# C51.net
KiCad netlist of a schematic drawn in EasyEDA Pro
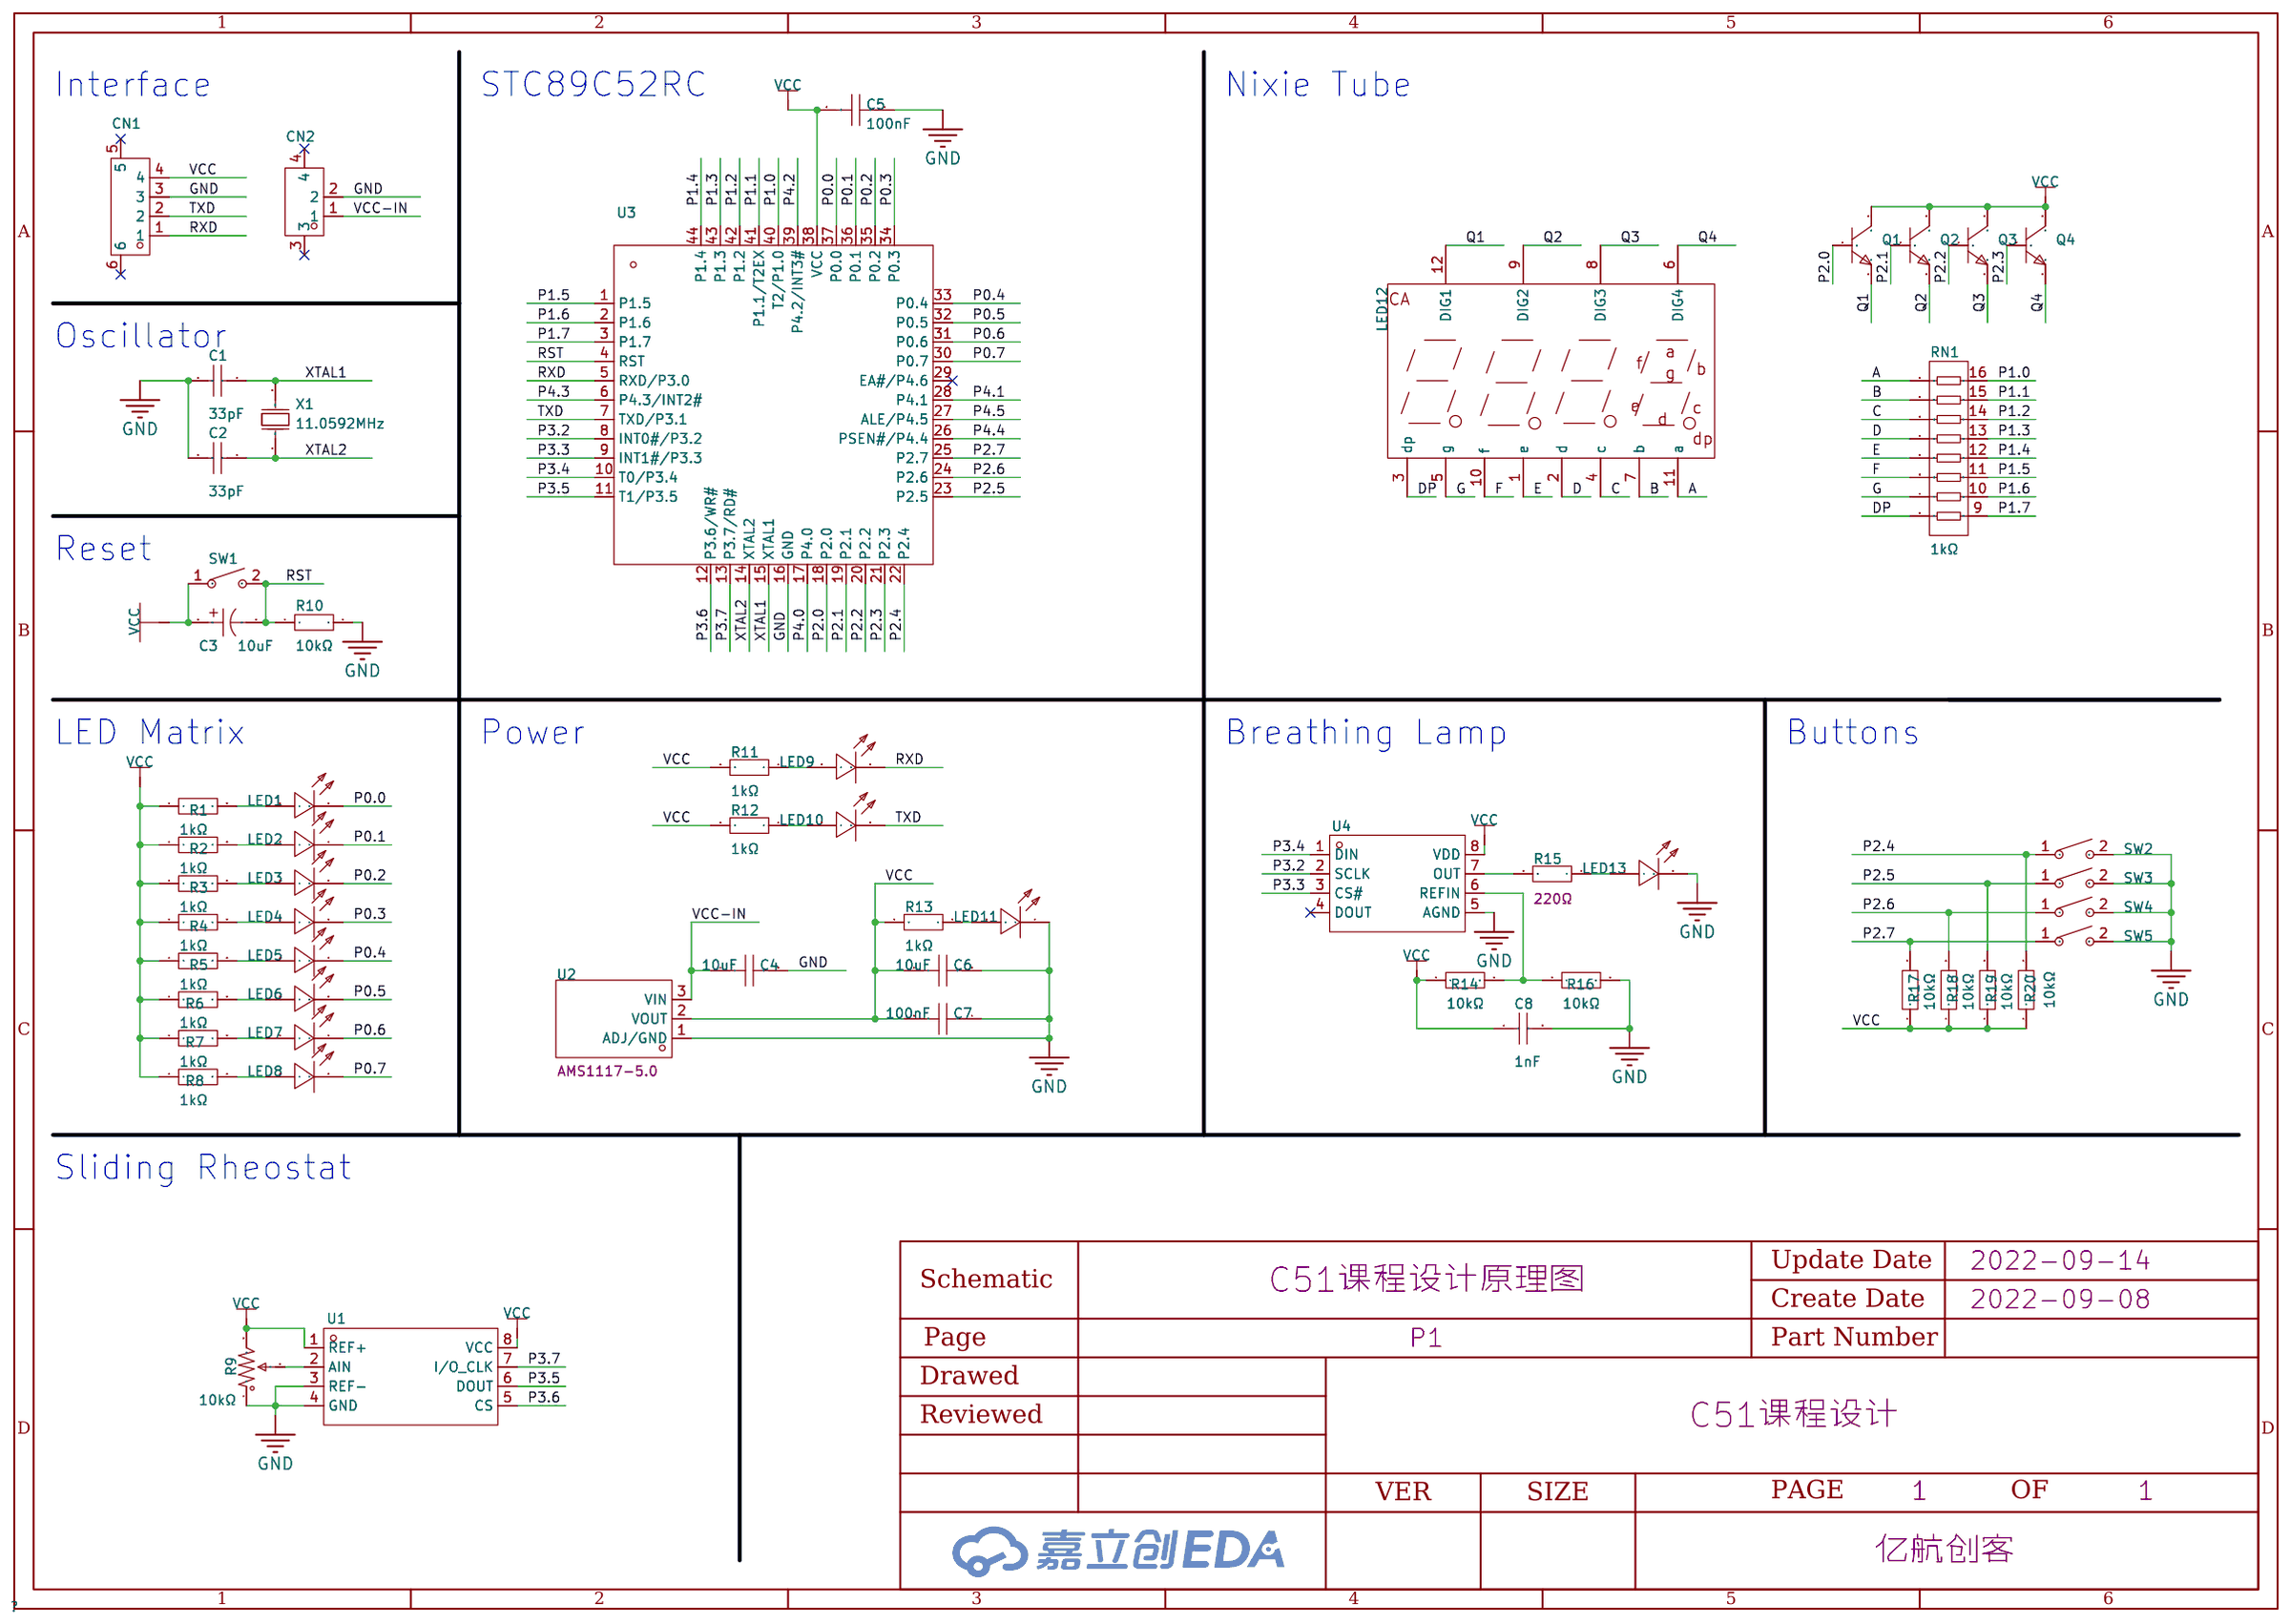
[diagram p0: schematic sheet]

(export (version "E")
  (design (tool "Eeschema 10.0.6"))
  (components
    (comp (ref "C1")
      (value "33pF")
      (footprint "easyedapro:C0402")
      (description "容值:33pF;精度:±5%;额定电压:50V;材质(温度系数):NP0;")
      (fields
        (field (name "Manufacturer Part") "CC0402JRNPO9BN330")
        (field (name "Manufacturer") "YAGEO(国巨)")
      )
      (libsource (lib "easyedapro") (part "CC0402JRNPO9BN330"))
    )
    (comp (ref "C2")
      (value "33pF")
      (footprint "easyedapro:C0402")
      (description "容值:33pF;精度:±5%;额定电压:50V;材质(温度系数):NP0;")
      (fields
        (field (name "Manufacturer Part") "CC0402JRNPO9BN330")
        (field (name "Manufacturer") "YAGEO(国巨)")
      )
      (libsource (lib "easyedapro") (part "CC0402JRNPO9BN330"))
    )
    (comp (ref "C3")
      (value "10uF")
      (footprint "easyedapro:CAP-SMD_L2.0-W1.3-FD")
      (description "容值:10uF;精度:±10%;额定电压:6.3V;漏电流:-;纹波电流:-;等效串联电阻:-;工作温度:-;")
      (fields
        (field (name "Manufacturer Part") "CA45-P-6.3V-10UF-K")
        (field (name "Manufacturer") "CEC(振华新云)")
      )
      (libsource (lib "easyedapro") (part "CA45-P-6.3V-10UF-K"))
    )
    (comp (ref "C4")
      (value "10uF")
      (footprint "easyedapro:C0402")
      (description "容值:10uF;精度:±20%;额定电压:-;温度系数:-;")
      (fields
        (field (name "Manufacturer Part") "ZRB15XR60J106ME12D")
        (field (name "Manufacturer") "muRata(村田)")
      )
      (libsource (lib "easyedapro") (part "ZRB15XR60J106ME12D"))
    )
    (comp (ref "C5")
      (value "100nF")
      (footprint "easyedapro:C0402")
      (description "容值:100nF;精度:±10%;额定电压:50V;材质(温度系数):X7R;")
      (fields (field (name "Manufacturer Part") "C1005X7R1H104KT000F") (field (name "Manufacturer") "TDK"))
      (libsource (lib "easyedapro") (part "C1005X7R1H104KT000F"))
    )
    (comp (ref "C6")
      (value "10uF")
      (footprint "easyedapro:C0402")
      (description "容值:10uF;精度:±20%;额定电压:-;温度系数:-;")
      (fields
        (field (name "Manufacturer Part") "ZRB15XR60J106ME12D")
        (field (name "Manufacturer") "muRata(村田)")
      )
      (libsource (lib "easyedapro") (part "ZRB15XR60J106ME12D"))
    )
    (comp (ref "C7")
      (value "100nF")
      (description "容值:100nF;精度:±10%;额定电压:50V;温度系数:X7R;")
      (fields (field (name "Manufacturer Part") "C1005X7R1H104KT000F") (field (name "Manufacturer") "TDK"))
      (libsource (lib "easyedapro") (part "C1005X7R1H104KT000F"))
    )
    (comp (ref "C8")
      (value "1nF")
      (footprint "easyedapro:C0402")
      (description "温度系数:X7R;容值:1nF;精度:±10%;额定电压:50V;")
      (fields (field (name "Manufacturer Part") "0402B102K500NT") (field (name "Manufacturer") "FH(风华)"))
      (libsource (lib "easyedapro") (part "0402B102K500NT"))
    )
    (comp (ref "CN1")
      (value "~")
      (footprint "easyedapro:CONN-SMD_4P-P1.00_HDGC_HDGC1002WR-S-4P")
      (description "参考系列:-;间距:1mm;插针结构:1x4P;排数:1;每排PIN数:4;行距:-;公母:公型插针;安装方式:卧贴;额定电流:1A;工作温度范围:-25~+70;")
      (fields (field (name "Manufacturer Part") "HDGC1002WR-S-4P") (field (name "Manufacturer") "HDGC(华德共创)"))
      (libsource (lib "easyedapro") (part "HDGC1002WR-S-4P"))
    )
    (comp (ref "CN2")
      (value "~")
      (footprint "easyedapro:CONN-SMD_HC-1.0-2PWT")
      (description "参考系列:-;间距:1mm;插针结构:1x2P;排数:1;每排PIN数:2;行距:-;公母:公型插针;安装方式:卧贴;额定电流:500mA;工作温度范围:-25~+85;")
      (fields (field (name "Manufacturer Part") "HC-1.0-2PWT") (field (name "Manufacturer") "HCTL(华灿天禄)"))
      (libsource (lib "easyedapro") (part "HC-1.0-2PWT"))
    )
    (comp (ref "LED1")
      (value "~")
      (footprint "easyedapro:LED0402-RD")
      (description "发光颜色:翠绿;")
      (fields (field (name "Manufacturer Part") "NCD0402G1") (field (name "Manufacturer") "国星光电"))
      (libsource (lib "easyedapro") (part "FC-F1005UGK-520M5"))
    )
    (comp (ref "LED2")
      (value "~")
      (footprint "easyedapro:LED0402-RD")
      (description "发光颜色:翠绿;")
      (fields (field (name "Manufacturer Part") "NCD0402G1") (field (name "Manufacturer") "国星光电"))
      (libsource (lib "easyedapro") (part "FC-F1005UGK-520M5"))
    )
    (comp (ref "LED3")
      (value "~")
      (footprint "easyedapro:LED0402-RD")
      (description "发光颜色:翠绿;")
      (fields (field (name "Manufacturer Part") "NCD0402G1") (field (name "Manufacturer") "国星光电"))
      (libsource (lib "easyedapro") (part "FC-F1005UGK-520M5"))
    )
    (comp (ref "LED4")
      (value "~")
      (footprint "easyedapro:LED0402-RD")
      (description "发光颜色:翠绿;")
      (fields (field (name "Manufacturer Part") "NCD0402G1") (field (name "Manufacturer") "国星光电"))
      (libsource (lib "easyedapro") (part "FC-F1005UGK-520M5"))
    )
    (comp (ref "LED5")
      (value "~")
      (footprint "easyedapro:LED0402-RD")
      (description "发光颜色:翠绿;")
      (fields (field (name "Manufacturer Part") "NCD0402G1") (field (name "Manufacturer") "国星光电"))
      (libsource (lib "easyedapro") (part "FC-F1005UGK-520M5"))
    )
    (comp (ref "LED6")
      (value "~")
      (footprint "easyedapro:LED0402-RD")
      (description "发光颜色:翠绿;")
      (fields (field (name "Manufacturer Part") "NCD0402G1") (field (name "Manufacturer") "国星光电"))
      (libsource (lib "easyedapro") (part "FC-F1005UGK-520M5"))
    )
    (comp (ref "LED7")
      (value "~")
      (footprint "easyedapro:LED0402-RD")
      (description "发光颜色:翠绿;")
      (fields (field (name "Manufacturer Part") "NCD0402G1") (field (name "Manufacturer") "国星光电"))
      (libsource (lib "easyedapro") (part "FC-F1005UGK-520M5"))
    )
    (comp (ref "LED8")
      (value "~")
      (footprint "easyedapro:LED0402-RD")
      (description "发光颜色:翠绿;")
      (fields (field (name "Manufacturer Part") "NCD0402G1") (field (name "Manufacturer") "国星光电"))
      (libsource (lib "easyedapro") (part "FC-F1005UGK-520M5"))
    )
    (comp (ref "LED9")
      (value "~")
      (footprint "easyedapro:LED0402-RD")
      (description "发光颜色:翠绿;")
      (fields (field (name "Manufacturer Part") "NCD0402G1") (field (name "Manufacturer") "国星光电"))
      (libsource (lib "easyedapro") (part "FC-F1005UGK-520M5"))
    )
    (comp (ref "LED10")
      (value "~")
      (footprint "easyedapro:LED0402-RD")
      (description "发光颜色:翠绿;")
      (fields (field (name "Manufacturer Part") "NCD0402G1") (field (name "Manufacturer") "国星光电"))
      (libsource (lib "easyedapro") (part "FC-F1005UGK-520M5"))
    )
    (comp (ref "LED11")
      (value "~")
      (footprint "easyedapro:LED0402-RD")
      (description "发光颜色:翠绿;")
      (fields (field (name "Manufacturer Part") "NCD0402G1") (field (name "Manufacturer") "国星光电"))
      (libsource (lib "easyedapro") (part "FC-F1005UGK-520M5"))
    )
    (comp (ref "LED12")
      (value "FJ2481BH")
      (footprint "easyedapro:LED-SEG-TH_FJ2481BH")
      (description "数码管位数:4;数码管的显示尺寸:0.28''(7.11mm);电路连线类型:阳极(正极);照明颜色:红色;")
      (fields (field (name "Manufacturer") "志浩"))
      (libsource (lib "easyedapro") (part "FJ2481BH"))
    )
    (comp (ref "LED13")
      (value "~")
      (footprint "easyedapro:LED0402-RD")
      (description "发光颜色:翠绿;")
      (fields (field (name "Manufacturer Part") "NCD0402G1") (field (name "Manufacturer") "国星光电"))
      (libsource (lib "easyedapro") (part "FC-F1005UGK-520M5"))
    )
    (comp (ref "Q1")
      (value "SS8050W Y1")
      (footprint "easyedapro:SOT-323-3_L2.1-W1.3-P1.30-LS2.3-BR")
      (fields (field (name "Manufacturer") "CBI(创基)"))
      (libsource (lib "easyedapro") (part "SS8050W"))
    )
    (comp (ref "Q2")
      (value "SS8050W Y1")
      (footprint "easyedapro:SOT-323-3_L2.1-W1.3-P1.30-LS2.3-BR")
      (fields (field (name "Manufacturer") "CBI(创基)"))
      (libsource (lib "easyedapro") (part "SS8050W"))
    )
    (comp (ref "Q3")
      (value "SS8050W Y1")
      (footprint "easyedapro:SOT-323-3_L2.1-W1.3-P1.30-LS2.3-BR")
      (fields (field (name "Manufacturer") "CBI(创基)"))
      (libsource (lib "easyedapro") (part "SS8050W"))
    )
    (comp (ref "Q4")
      (value "SS8050W Y1")
      (footprint "easyedapro:SOT-323-3_L2.1-W1.3-P1.30-LS2.3-BR")
      (fields (field (name "Manufacturer") "CBI(创基)"))
      (libsource (lib "easyedapro") (part "SS8050W"))
    )
    (comp (ref "R1")
      (value "1kΩ")
      (footprint "easyedapro:R0402")
      (description "阻值:10kΩ;精度:±1%;功率:1/16W;温度系数:±100ppm/;最大工作电压:50V;工作温度范围:-55~+155;")
      (fields (field (name "Manufacturer Part") "WR04X1002FTL") (field (name "Manufacturer") "华新科(Walsin)"))
      (libsource (lib "easyedapro") (part "WR04X1002FTL"))
    )
    (comp (ref "R2")
      (value "1kΩ")
      (footprint "easyedapro:R0402")
      (description "阻值:10kΩ;精度:±1%;功率:1/16W;温度系数:±100ppm/;最大工作电压:50V;工作温度范围:-55~+155;")
      (fields (field (name "Manufacturer Part") "WR04X1002FTL") (field (name "Manufacturer") "华新科(Walsin)"))
      (libsource (lib "easyedapro") (part "WR04X1002FTL"))
    )
    (comp (ref "R3")
      (value "1kΩ")
      (footprint "easyedapro:R0402")
      (description "阻值:10kΩ;精度:±1%;功率:1/16W;温度系数:±100ppm/;最大工作电压:50V;工作温度范围:-55~+155;")
      (fields (field (name "Manufacturer Part") "WR04X1002FTL") (field (name "Manufacturer") "华新科(Walsin)"))
      (libsource (lib "easyedapro") (part "WR04X1002FTL"))
    )
    (comp (ref "R4")
      (value "1kΩ")
      (footprint "easyedapro:R0402")
      (description "阻值:10kΩ;精度:±1%;功率:1/16W;温度系数:±100ppm/;最大工作电压:50V;工作温度范围:-55~+155;")
      (fields (field (name "Manufacturer Part") "WR04X1002FTL") (field (name "Manufacturer") "华新科(Walsin)"))
      (libsource (lib "easyedapro") (part "WR04X1002FTL"))
    )
    (comp (ref "R5")
      (value "1kΩ")
      (footprint "easyedapro:R0402")
      (description "阻值:10kΩ;精度:±1%;功率:1/16W;温度系数:±100ppm/;最大工作电压:50V;工作温度范围:-55~+155;")
      (fields (field (name "Manufacturer Part") "WR04X1002FTL") (field (name "Manufacturer") "华新科(Walsin)"))
      (libsource (lib "easyedapro") (part "WR04X1002FTL"))
    )
    (comp (ref "R6")
      (value "1kΩ")
      (footprint "easyedapro:R0402")
      (description "阻值:10kΩ;精度:±1%;功率:1/16W;温度系数:±100ppm/;最大工作电压:50V;工作温度范围:-55~+155;")
      (fields (field (name "Manufacturer Part") "WR04X1002FTL") (field (name "Manufacturer") "华新科(Walsin)"))
      (libsource (lib "easyedapro") (part "WR04X1002FTL"))
    )
    (comp (ref "R7")
      (value "1kΩ")
      (footprint "easyedapro:R0402")
      (description "阻值:10kΩ;精度:±1%;功率:1/16W;温度系数:±100ppm/;最大工作电压:50V;工作温度范围:-55~+155;")
      (fields (field (name "Manufacturer Part") "WR04X1002FTL") (field (name "Manufacturer") "华新科(Walsin)"))
      (libsource (lib "easyedapro") (part "WR04X1002FTL"))
    )
    (comp (ref "R8")
      (value "1kΩ")
      (footprint "easyedapro:R0402")
      (description "阻值:10kΩ;精度:±1%;功率:1/16W;温度系数:±100ppm/;最大工作电压:50V;工作温度范围:-55~+155;")
      (fields (field (name "Manufacturer Part") "WR04X1002FTL") (field (name "Manufacturer") "华新科(Walsin)"))
      (libsource (lib "easyedapro") (part "WR04X1002FTL"))
    )
    (comp (ref "R9")
      (value "10kΩ")
      (footprint "easyedapro:RES-ADJ-TH_3362P")
      (description "阻值:10kΩ;精度:±10%;温度系数:±250ppm/;")
      (fields (field (name "Manufacturer Part") "3362P-1-103") (field (name "Manufacturer") "BOCHEN(博晨)"))
      (libsource (lib "easyedapro") (part "3362P-1-103_C118956"))
    )
    (comp (ref "R10")
      (value "10kΩ")
      (footprint "easyedapro:R0402")
      (description "阻值:10kΩ;精度:±1%;功率:1/16W;温度系数:±100ppm/;最大工作电压:50V;工作温度范围:-55~+155;")
      (fields (field (name "Manufacturer Part") "WR04X1002FTL") (field (name "Manufacturer") "华新科(Walsin)"))
      (libsource (lib "easyedapro") (part "WR04X1002FTL"))
    )
    (comp (ref "R11")
      (value "1kΩ")
      (footprint "easyedapro:R0402")
      (description "电阻类型:厚膜电阻;阻值:1kΩ;精度:±1%;功率:62.5mW;温度系数:±100ppm/;最大工作电压:50V;工作温度范围:-55~+155;")
      (fields
        (field (name "Manufacturer Part") "0402WGF1001TCE")
        (field (name "Manufacturer") "UNI-ROYAL(厚声)")
      )
      (libsource (lib "easyedapro") (part "0402WGF1001TCE"))
    )
    (comp (ref "R12")
      (value "1kΩ")
      (footprint "easyedapro:R0402")
      (description "电阻类型:厚膜电阻;阻值:1kΩ;精度:±1%;功率:62.5mW;温度系数:±100ppm/;最大工作电压:50V;工作温度范围:-55~+155;")
      (fields
        (field (name "Manufacturer Part") "0402WGF1001TCE")
        (field (name "Manufacturer") "UNI-ROYAL(厚声)")
      )
      (libsource (lib "easyedapro") (part "0402WGF1001TCE"))
    )
    (comp (ref "R13")
      (value "1kΩ")
      (footprint "easyedapro:R0402")
      (description "电阻类型:厚膜电阻;阻值:1kΩ;精度:±1%;功率:62.5mW;温度系数:±100ppm/;最大工作电压:50V;工作温度范围:-55~+155;")
      (fields
        (field (name "Manufacturer Part") "0402WGF1001TCE")
        (field (name "Manufacturer") "UNI-ROYAL(厚声)")
      )
      (libsource (lib "easyedapro") (part "0402WGF1001TCE"))
    )
    (comp (ref "R14")
      (value "10kΩ")
      (footprint "easyedapro:R0402")
      (description "阻值:10kΩ;精度:±1%;功率:1/16W;温度系数:±100ppm/;最大工作电压:50V;工作温度范围:-55~+155;")
      (fields (field (name "Manufacturer Part") "WR04X1002FTL") (field (name "Manufacturer") "华新科(Walsin)"))
      (libsource (lib "easyedapro") (part "WR04X1002FTL"))
    )
    (comp (ref "R15")
      (value "0402WGF2200TCE")
      (footprint "easyedapro:R0402")
      (fields (field (name "Manufacturer") "UNI-ROYAL(厚声)") (field (name "LCSC Part Name") "220Ω"))
      (libsource (lib "easyedapro") (part "0402WGF2200TCE"))
    )
    (comp (ref "R16")
      (value "10kΩ")
      (footprint "easyedapro:R0402")
      (description "阻值:10kΩ;精度:±1%;功率:1/16W;温度系数:±100ppm/;最大工作电压:50V;工作温度范围:-55~+155;")
      (fields (field (name "Manufacturer Part") "WR04X1002FTL") (field (name "Manufacturer") "华新科(Walsin)"))
      (libsource (lib "easyedapro") (part "WR04X1002FTL"))
    )
    (comp (ref "R17")
      (value "10kΩ")
      (footprint "easyedapro:R0402")
      (description "阻值:10kΩ;精度:±1%;功率:1/16W;温度系数:±100ppm/;最大工作电压:50V;工作温度范围:-55~+155;")
      (fields (field (name "Manufacturer Part") "WR04X1002FTL") (field (name "Manufacturer") "华新科(Walsin)"))
      (libsource (lib "easyedapro") (part "WR04X1002FTL"))
    )
    (comp (ref "R18")
      (value "10kΩ")
      (footprint "easyedapro:R0402")
      (description "阻值:10kΩ;精度:±1%;功率:1/16W;温度系数:±100ppm/;最大工作电压:50V;工作温度范围:-55~+155;")
      (fields (field (name "Manufacturer Part") "WR04X1002FTL") (field (name "Manufacturer") "华新科(Walsin)"))
      (libsource (lib "easyedapro") (part "WR04X1002FTL"))
    )
    (comp (ref "R19")
      (value "10kΩ")
      (footprint "easyedapro:R0402")
      (description "阻值:10kΩ;精度:±1%;功率:1/16W;温度系数:±100ppm/;最大工作电压:50V;工作温度范围:-55~+155;")
      (fields (field (name "Manufacturer Part") "WR04X1002FTL") (field (name "Manufacturer") "华新科(Walsin)"))
      (libsource (lib "easyedapro") (part "WR04X1002FTL"))
    )
    (comp (ref "R20")
      (value "10kΩ")
      (footprint "easyedapro:R0402")
      (description "阻值:10kΩ;精度:±1%;功率:1/16W;温度系数:±100ppm/;最大工作电压:50V;工作温度范围:-55~+155;")
      (fields (field (name "Manufacturer Part") "WR04X1002FTL") (field (name "Manufacturer") "华新科(Walsin)"))
      (libsource (lib "easyedapro") (part "WR04X1002FTL"))
    )
    (comp (ref "RN1")
      (value "1kΩ")
      (footprint "easyedapro:RES-ARRAY-SMD_0603-16P-L4.0-W1.6-BL")
      (description "阻值:1kΩ;单个元件功率:62.5mW;电阻器数:8;引脚数:16;")
      (fields
        (field (name "Manufacturer Part") "16P8WGJ0102T4E")
        (field (name "Manufacturer") "UNI-ROYAL(厚声)")
      )
      (libsource (lib "easyedapro") (part "16P8WGJ0102T4E"))
    )
    (comp (ref "SW1")
      (value "~")
      (footprint "easyedapro:SW-SMD_ST-1185S")
      (fields (field (name "Manufacturer Part") "ST-1185S") (field (name "Manufacturer") "RISHENG(日昇)"))
      (libsource (lib "easyedapro") (part "ST-1185S"))
    )
    (comp (ref "SW2")
      (value "~")
      (footprint "easyedapro:SW-SMD_ST-1185S")
      (fields (field (name "Manufacturer Part") "ST-1185S") (field (name "Manufacturer") "RISHENG(日昇)"))
      (libsource (lib "easyedapro") (part "ST-1185S"))
    )
    (comp (ref "SW3")
      (value "~")
      (footprint "easyedapro:SW-SMD_ST-1185S")
      (fields (field (name "Manufacturer Part") "ST-1185S") (field (name "Manufacturer") "RISHENG(日昇)"))
      (libsource (lib "easyedapro") (part "ST-1185S"))
    )
    (comp (ref "SW4")
      (value "~")
      (footprint "easyedapro:SW-SMD_ST-1185S")
      (fields (field (name "Manufacturer Part") "ST-1185S") (field (name "Manufacturer") "RISHENG(日昇)"))
      (libsource (lib "easyedapro") (part "ST-1185S"))
    )
    (comp (ref "SW5")
      (value "~")
      (footprint "easyedapro:SW-SMD_ST-1185S")
      (fields (field (name "Manufacturer Part") "ST-1185S") (field (name "Manufacturer") "RISHENG(日昇)"))
      (libsource (lib "easyedapro") (part "ST-1185S"))
    )
    (comp (ref "U1")
      (value "XL549")
      (footprint "easyedapro:SOP-8_L5.0-W4.0-P1.27-LS6.0-BL")
      (fields (field (name "Manufacturer") "XINLUDA(信路达)"))
      (libsource (lib "easyedapro") (part "XL549"))
    )
    (comp (ref "U2")
      (value "~")
      (footprint "easyedapro:SOT-89-3_L4.5-W2.5-P1.50-LS4.2-BR")
      (description "输出类型:-;")
      (fields (field (name "Manufacturer Part") "AMS1117-5.0") (field (name "Manufacturer") "JSMSEMI(杰盛微)"))
      (libsource (lib "easyedapro") (part "AMS1117-5.0_C2718490"))
    )
    (comp (ref "U3")
      (value "STC89C52RC-40I")
      (footprint "easyedapro:LQFP-44_L10.0-W10.0-P0.80-LS12.0-BL")
      (description "工作电压:3.3V ~ 5.5V;CPU内核:8051;主频（MAX):80MHz;")
      (fields (field (name "Manufacturer") "STC(宏晶)"))
      (libsource (lib "easyedapro") (part "STC89C52RC-40I_C8707"))
    )
    (comp (ref "U4")
      (value "HGC5615CM/TR")
      (footprint "easyedapro:SOP-8_L4.9-W3.9-P1.27-LS6.0-BL-1")
      (description "趋稳时间为 12.5us 并具备上电复位功能的 10 位、单通道、低功耗 DAC")
      (fields (field (name "Manufacturer") "HGSEMI(华冠)"))
      (libsource (lib "easyedapro") (part "HGC5615CM/TR"))
    )
    (comp (ref "X1")
      (value "11.0592MHz")
      (footprint "easyedapro:OSC-SMD_L5.0-W3.2")
      (description "晶振类型:贴片无源晶振;频率:11.0592MHz;频率公差:±10ppm;频率稳定度:±50ppm;负载电容:20pF;工作温度:-40~+85;")
      (fields (field (name "Manufacturer Part") "X5032110592MSB2GI") (field (name "Manufacturer") "YXC扬兴科技"))
      (libsource (lib "easyedapro") (part "X5032110592MSB2GI"))
    )
  )
  (nets
    (net (code "1") (name "/A") (class "Default")
      (node (ref "LED12") (pin "11") (pinfunction "a_11") (pintype "input"))
      (node (ref "RN1") (pin "1") (pinfunction "1_1") (pintype "input"))
    )
    (net (code "2") (name "/B") (class "Default")
      (node (ref "LED12") (pin "7") (pinfunction "b_7") (pintype "input"))
      (node (ref "RN1") (pin "2") (pinfunction "2_2") (pintype "input"))
    )
    (net (code "3") (name "/C") (class "Default")
      (node (ref "LED12") (pin "4") (pinfunction "c_4") (pintype "input"))
      (node (ref "RN1") (pin "3") (pinfunction "3_3") (pintype "input"))
    )
    (net (code "4") (name "/D") (class "Default")
      (node (ref "LED12") (pin "2") (pinfunction "d_2") (pintype "input"))
      (node (ref "RN1") (pin "4") (pinfunction "4_4") (pintype "input"))
    )
    (net (code "5") (name "/DP") (class "Default")
      (node (ref "LED12") (pin "3") (pinfunction "dp_3") (pintype "input"))
      (node (ref "RN1") (pin "8") (pinfunction "8_8") (pintype "input"))
    )
    (net (code "6") (name "/E") (class "Default")
      (node (ref "LED12") (pin "1") (pinfunction "e_1") (pintype "input"))
      (node (ref "RN1") (pin "5") (pinfunction "5_5") (pintype "input"))
    )
    (net (code "7") (name "/F") (class "Default")
      (node (ref "LED12") (pin "10") (pinfunction "f_10") (pintype "input"))
      (node (ref "RN1") (pin "6") (pinfunction "6_6") (pintype "input"))
    )
    (net (code "8") (name "/G") (class "Default")
      (node (ref "LED12") (pin "5") (pinfunction "g_5") (pintype "input"))
      (node (ref "RN1") (pin "7") (pinfunction "7_7") (pintype "input"))
    )
    (net (code "9") (name "/P0.0") (class "Default")
      (node (ref "LED1") (pin "1") (pinfunction "K_1") (pintype "input"))
      (node (ref "U3") (pin "37") (pinfunction "P0.0_37") (pintype "input"))
    )
    (net (code "10") (name "/P0.1") (class "Default")
      (node (ref "LED2") (pin "1") (pinfunction "K_1") (pintype "input"))
      (node (ref "U3") (pin "36") (pinfunction "P0.1_36") (pintype "input"))
    )
    (net (code "11") (name "/P0.2") (class "Default")
      (node (ref "LED3") (pin "1") (pinfunction "K_1") (pintype "input"))
      (node (ref "U3") (pin "35") (pinfunction "P0.2_35") (pintype "input"))
    )
    (net (code "12") (name "/P0.3") (class "Default")
      (node (ref "LED4") (pin "1") (pinfunction "K_1") (pintype "input"))
      (node (ref "U3") (pin "34") (pinfunction "P0.3_34") (pintype "input"))
    )
    (net (code "13") (name "/P0.4") (class "Default")
      (node (ref "LED5") (pin "1") (pinfunction "K_1") (pintype "input"))
      (node (ref "U3") (pin "33") (pinfunction "P0.4_33") (pintype "input"))
    )
    (net (code "14") (name "/P0.5") (class "Default")
      (node (ref "LED6") (pin "1") (pinfunction "K_1") (pintype "input"))
      (node (ref "U3") (pin "32") (pinfunction "P0.5_32") (pintype "input"))
    )
    (net (code "15") (name "/P0.6") (class "Default")
      (node (ref "LED7") (pin "1") (pinfunction "K_1") (pintype "input"))
      (node (ref "U3") (pin "31") (pinfunction "P0.6_31") (pintype "input"))
    )
    (net (code "16") (name "/P0.7") (class "Default")
      (node (ref "LED8") (pin "1") (pinfunction "K_1") (pintype "input"))
      (node (ref "U3") (pin "30") (pinfunction "P0.7_30") (pintype "input"))
    )
    (net (code "17") (name "/P1.0") (class "Default")
      (node (ref "RN1") (pin "16") (pinfunction "16_16") (pintype "input"))
      (node (ref "U3") (pin "40") (pinfunction "T2/P1.0_40") (pintype "input"))
    )
    (net (code "18") (name "/P1.1") (class "Default")
      (node (ref "RN1") (pin "15") (pinfunction "15_15") (pintype "input"))
      (node (ref "U3") (pin "41") (pinfunction "P1.1/T2EX_41") (pintype "input"))
    )
    (net (code "19") (name "/P1.2") (class "Default")
      (node (ref "RN1") (pin "14") (pinfunction "14_14") (pintype "input"))
      (node (ref "U3") (pin "42") (pinfunction "P1.2_42") (pintype "input"))
    )
    (net (code "20") (name "/P1.3") (class "Default")
      (node (ref "RN1") (pin "13") (pinfunction "13_13") (pintype "input"))
      (node (ref "U3") (pin "43") (pinfunction "P1.3_43") (pintype "input"))
    )
    (net (code "21") (name "/P1.4") (class "Default")
      (node (ref "RN1") (pin "12") (pinfunction "12_12") (pintype "input"))
      (node (ref "U3") (pin "44") (pinfunction "P1.4_44") (pintype "input"))
    )
    (net (code "22") (name "/P1.5") (class "Default")
      (node (ref "RN1") (pin "11") (pinfunction "11_11") (pintype "input"))
      (node (ref "U3") (pin "1") (pinfunction "P1.5_1") (pintype "input"))
    )
    (net (code "23") (name "/P1.6") (class "Default")
      (node (ref "RN1") (pin "10") (pinfunction "10_10") (pintype "input"))
      (node (ref "U3") (pin "2") (pinfunction "P1.6_2") (pintype "input"))
    )
    (net (code "24") (name "/P1.7") (class "Default")
      (node (ref "RN1") (pin "9") (pinfunction "9_9") (pintype "input"))
      (node (ref "U3") (pin "3") (pinfunction "P1.7_3") (pintype "input"))
    )
    (net (code "25") (name "/P2.0") (class "Default")
      (node (ref "Q1") (pin "1") (pinfunction "B_1") (pintype "input"))
      (node (ref "U3") (pin "18") (pinfunction "P2.0_18") (pintype "input"))
    )
    (net (code "26") (name "/P2.1") (class "Default")
      (node (ref "Q2") (pin "1") (pinfunction "B_1") (pintype "input"))
      (node (ref "U3") (pin "19") (pinfunction "P2.1_19") (pintype "input"))
    )
    (net (code "27") (name "/P2.2") (class "Default")
      (node (ref "Q3") (pin "1") (pinfunction "B_1") (pintype "input"))
      (node (ref "U3") (pin "20") (pinfunction "P2.2_20") (pintype "input"))
    )
    (net (code "28") (name "/P2.3") (class "Default")
      (node (ref "Q4") (pin "1") (pinfunction "B_1") (pintype "input"))
      (node (ref "U3") (pin "21") (pinfunction "P2.3_21") (pintype "input"))
    )
    (net (code "29") (name "/P2.4") (class "Default")
      (node (ref "R20") (pin "2") (pinfunction "2_2") (pintype "input"))
      (node (ref "SW2") (pin "1") (pinfunction "1_1") (pintype "input"))
      (node (ref "U3") (pin "22") (pinfunction "P2.4_22") (pintype "input"))
    )
    (net (code "30") (name "/P2.5") (class "Default")
      (node (ref "R19") (pin "2") (pinfunction "2_2") (pintype "input"))
      (node (ref "SW3") (pin "1") (pinfunction "1_1") (pintype "input"))
      (node (ref "U3") (pin "23") (pinfunction "P2.5_23") (pintype "input"))
    )
    (net (code "31") (name "/P2.6") (class "Default")
      (node (ref "R18") (pin "2") (pinfunction "2_2") (pintype "input"))
      (node (ref "SW4") (pin "1") (pinfunction "1_1") (pintype "input"))
      (node (ref "U3") (pin "24") (pinfunction "P2.6_24") (pintype "input"))
    )
    (net (code "32") (name "/P2.7") (class "Default")
      (node (ref "R17") (pin "2") (pinfunction "2_2") (pintype "input"))
      (node (ref "SW5") (pin "1") (pinfunction "1_1") (pintype "input"))
      (node (ref "U3") (pin "25") (pinfunction "P2.7_25") (pintype "input"))
    )
    (net (code "33") (name "/P3.2") (class "Default")
      (node (ref "U3") (pin "8") (pinfunction "INT0#/P3.2_8") (pintype "input"))
      (node (ref "U4") (pin "2") (pinfunction "SCLK_2") (pintype "input"))
    )
    (net (code "34") (name "/P3.3") (class "Default")
      (node (ref "U3") (pin "9") (pinfunction "INT1#/P3.3_9") (pintype "input"))
      (node (ref "U4") (pin "3") (pinfunction "CS#_3") (pintype "input"))
    )
    (net (code "35") (name "/P3.4") (class "Default")
      (node (ref "U3") (pin "10") (pinfunction "T0/P3.4_10") (pintype "input"))
      (node (ref "U4") (pin "1") (pinfunction "DIN_1") (pintype "input"))
    )
    (net (code "36") (name "/P3.5") (class "Default")
      (node (ref "U1") (pin "6") (pinfunction "DOUT_6") (pintype "input"))
      (node (ref "U3") (pin "11") (pinfunction "T1/P3.5_11") (pintype "input"))
    )
    (net (code "37") (name "/P3.6") (class "Default")
      (node (ref "U1") (pin "5") (pinfunction "CS_5") (pintype "input"))
      (node (ref "U3") (pin "12") (pinfunction "P3.6/WR#_12") (pintype "input"))
    )
    (net (code "38") (name "/P3.7") (class "Default")
      (node (ref "U1") (pin "7") (pinfunction "I/O_CLK_7") (pintype "input"))
      (node (ref "U3") (pin "13") (pinfunction "P3.7/RD#_13") (pintype "input"))
    )
    (net (code "39") (name "/P4.0") (class "Default")
      (node (ref "U3") (pin "17") (pinfunction "P4.0_17") (pintype "input"))
    )
    (net (code "40") (name "/P4.1") (class "Default")
      (node (ref "U3") (pin "28") (pinfunction "P4.1_28") (pintype "input"))
    )
    (net (code "41") (name "/P4.2") (class "Default")
      (node (ref "U3") (pin "39") (pinfunction "P4.2/INT3#_39") (pintype "input"))
    )
    (net (code "42") (name "/P4.3") (class "Default")
      (node (ref "U3") (pin "6") (pinfunction "P4.3/INT2#_6") (pintype "input"))
    )
    (net (code "43") (name "/P4.4") (class "Default")
      (node (ref "U3") (pin "26") (pinfunction "PSEN#/P4.4_26") (pintype "input"))
    )
    (net (code "44") (name "/P4.5") (class "Default")
      (node (ref "U3") (pin "27") (pinfunction "ALE/P4.5_27") (pintype "input"))
    )
    (net (code "45") (name "/Q1") (class "Default")
      (node (ref "LED12") (pin "12") (pinfunction "DIG1_12") (pintype "input"))
      (node (ref "Q1") (pin "2") (pinfunction "E_2") (pintype "input"))
    )
    (net (code "46") (name "/Q2") (class "Default")
      (node (ref "LED12") (pin "9") (pinfunction "DIG2_9") (pintype "input"))
      (node (ref "Q2") (pin "2") (pinfunction "E_2") (pintype "input"))
    )
    (net (code "47") (name "/Q3") (class "Default")
      (node (ref "LED12") (pin "8") (pinfunction "DIG3_8") (pintype "input"))
      (node (ref "Q3") (pin "2") (pinfunction "E_2") (pintype "input"))
    )
    (net (code "48") (name "/Q4") (class "Default")
      (node (ref "LED12") (pin "6") (pinfunction "DIG4_6") (pintype "input"))
      (node (ref "Q4") (pin "2") (pinfunction "E_2") (pintype "input"))
    )
    (net (code "49") (name "/RST") (class "Default")
      (node (ref "C3") (pin "2") (pinfunction "2_2") (pintype "input"))
      (node (ref "R10") (pin "1") (pinfunction "1_1") (pintype "input"))
      (node (ref "SW1") (pin "2") (pinfunction "2_2") (pintype "input"))
      (node (ref "U3") (pin "4") (pinfunction "RST_4") (pintype "input"))
    )
    (net (code "50") (name "/RXD") (class "Default")
      (node (ref "CN1") (pin "1") (pinfunction "1_1") (pintype "input"))
      (node (ref "LED9") (pin "1") (pinfunction "K_1") (pintype "input"))
      (node (ref "U3") (pin "5") (pinfunction "RXD/P3.0_5") (pintype "input"))
    )
    (net (code "51") (name "/TXD") (class "Default")
      (node (ref "CN1") (pin "2") (pinfunction "2_2") (pintype "input"))
      (node (ref "LED10") (pin "1") (pinfunction "K_1") (pintype "input"))
      (node (ref "U3") (pin "7") (pinfunction "TXD/P3.1_7") (pintype "input"))
    )
    (net (code "52") (name "/VCC-IN") (class "Default")
      (node (ref "C4") (pin "1") (pinfunction "1_1") (pintype "input"))
      (node (ref "CN2") (pin "1") (pinfunction "1_1") (pintype "input"))
      (node (ref "U2") (pin "3") (pinfunction "VIN_3") (pintype "input"))
    )
    (net (code "53") (name "/XTAL1") (class "Default")
      (node (ref "C1") (pin "2") (pinfunction "2_2") (pintype "input"))
      (node (ref "U3") (pin "15") (pinfunction "XTAL1_15") (pintype "input"))
      (node (ref "X1") (pin "2") (pinfunction "OSC2_2") (pintype "input"))
    )
    (net (code "54") (name "/XTAL2") (class "Default")
      (node (ref "C2") (pin "2") (pinfunction "2_2") (pintype "input"))
      (node (ref "U3") (pin "14") (pinfunction "XTAL2_14") (pintype "input"))
      (node (ref "X1") (pin "1") (pinfunction "OSC1_1") (pintype "input"))
    )
    (net (code "55") (name "GND") (class "Default")
      (node (ref "C1") (pin "1") (pinfunction "1_1") (pintype "input"))
      (node (ref "C2") (pin "1") (pinfunction "1_1") (pintype "input"))
      (node (ref "C4") (pin "2") (pinfunction "2_2") (pintype "input"))
      (node (ref "C5") (pin "1") (pinfunction "1_1") (pintype "input"))
      (node (ref "C6") (pin "2") (pinfunction "2_2") (pintype "input"))
      (node (ref "C7") (pin "1") (pinfunction "1_1") (pintype "input"))
      (node (ref "C8") (pin "2") (pinfunction "2_2") (pintype "input"))
      (node (ref "CN1") (pin "3") (pinfunction "3_3") (pintype "input"))
      (node (ref "CN2") (pin "2") (pinfunction "2_2") (pintype "input"))
      (node (ref "LED11") (pin "1") (pinfunction "K_1") (pintype "input"))
      (node (ref "LED13") (pin "1") (pinfunction "K_1") (pintype "input"))
      (node (ref "R10") (pin "2") (pinfunction "2_2") (pintype "input"))
      (node (ref "R16") (pin "2") (pinfunction "2_2") (pintype "input"))
      (node (ref "R9") (pin "1") (pinfunction "1_1") (pintype "input"))
      (node (ref "SW2") (pin "2") (pinfunction "2_2") (pintype "input"))
      (node (ref "SW3") (pin "2") (pinfunction "2_2") (pintype "input"))
      (node (ref "SW4") (pin "2") (pinfunction "2_2") (pintype "input"))
      (node (ref "SW5") (pin "2") (pinfunction "2_2") (pintype "input"))
      (node (ref "U1") (pin "3") (pinfunction "REF-_3") (pintype "input"))
      (node (ref "U1") (pin "4") (pinfunction "GND_4") (pintype "input"))
      (node (ref "U2") (pin "1") (pinfunction "ADJ/GND_1") (pintype "input"))
      (node (ref "U3") (pin "16") (pinfunction "GND_16") (pintype "input"))
      (node (ref "U4") (pin "5") (pinfunction "AGND_5") (pintype "input"))
    )
    (net (code "56") (name "Net-(LED1-A)") (class "Default")
      (node (ref "LED1") (pin "2") (pinfunction "A_2") (pintype "input"))
      (node (ref "R1") (pin "2") (pinfunction "2_2") (pintype "input"))
    )
    (net (code "57") (name "Net-(LED2-A)") (class "Default")
      (node (ref "LED2") (pin "2") (pinfunction "A_2") (pintype "input"))
      (node (ref "R2") (pin "2") (pinfunction "2_2") (pintype "input"))
    )
    (net (code "58") (name "Net-(LED3-A)") (class "Default")
      (node (ref "LED3") (pin "2") (pinfunction "A_2") (pintype "input"))
      (node (ref "R3") (pin "2") (pinfunction "2_2") (pintype "input"))
    )
    (net (code "59") (name "Net-(LED4-A)") (class "Default")
      (node (ref "LED4") (pin "2") (pinfunction "A_2") (pintype "input"))
      (node (ref "R4") (pin "2") (pinfunction "2_2") (pintype "input"))
    )
    (net (code "60") (name "Net-(LED5-A)") (class "Default")
      (node (ref "LED5") (pin "2") (pinfunction "A_2") (pintype "input"))
      (node (ref "R5") (pin "2") (pinfunction "2_2") (pintype "input"))
    )
    (net (code "61") (name "Net-(LED6-A)") (class "Default")
      (node (ref "LED6") (pin "2") (pinfunction "A_2") (pintype "input"))
      (node (ref "R6") (pin "2") (pinfunction "2_2") (pintype "input"))
    )
    (net (code "62") (name "Net-(LED7-A)") (class "Default")
      (node (ref "LED7") (pin "2") (pinfunction "A_2") (pintype "input"))
      (node (ref "R7") (pin "2") (pinfunction "2_2") (pintype "input"))
    )
    (net (code "63") (name "Net-(LED8-A)") (class "Default")
      (node (ref "LED8") (pin "2") (pinfunction "A_2") (pintype "input"))
      (node (ref "R8") (pin "2") (pinfunction "2_2") (pintype "input"))
    )
    (net (code "64") (name "Net-(LED9-A)") (class "Default")
      (node (ref "LED9") (pin "2") (pinfunction "A_2") (pintype "input"))
      (node (ref "R11") (pin "1") (pinfunction "1_1") (pintype "input"))
    )
    (net (code "65") (name "Net-(LED10-A)") (class "Default")
      (node (ref "LED10") (pin "2") (pinfunction "A_2") (pintype "input"))
      (node (ref "R12") (pin "1") (pinfunction "1_1") (pintype "input"))
    )
    (net (code "66") (name "Net-(LED11-A)") (class "Default")
      (node (ref "LED11") (pin "2") (pinfunction "A_2") (pintype "input"))
      (node (ref "R13") (pin "1") (pinfunction "1_1") (pintype "input"))
    )
    (net (code "67") (name "Net-(LED13-A)") (class "Default")
      (node (ref "LED13") (pin "2") (pinfunction "A_2") (pintype "input"))
      (node (ref "R15") (pin "1") (pinfunction "1_1") (pintype "input"))
    )
    (net (code "68") (name "Net-(U1-AIN)") (class "Default")
      (node (ref "R9") (pin "2") (pinfunction "2_2") (pintype "input"))
      (node (ref "U1") (pin "2") (pinfunction "AIN_2") (pintype "input"))
    )
    (net (code "69") (name "Net-(U4-OUT)") (class "Default")
      (node (ref "R15") (pin "2") (pinfunction "2_2") (pintype "input"))
      (node (ref "U4") (pin "7") (pinfunction "OUT_7") (pintype "input"))
    )
    (net (code "70") (name "Net-(U4-REFIN)") (class "Default")
      (node (ref "R14") (pin "2") (pinfunction "2_2") (pintype "input"))
      (node (ref "R16") (pin "1") (pinfunction "1_1") (pintype "input"))
      (node (ref "U4") (pin "6") (pinfunction "REFIN_6") (pintype "input"))
    )
    (net (code "71") (name "VCC") (class "Default")
      (node (ref "C3") (pin "1") (pinfunction "1_1") (pintype "input"))
      (node (ref "C5") (pin "2") (pinfunction "2_2") (pintype "input"))
      (node (ref "C6") (pin "1") (pinfunction "1_1") (pintype "input"))
      (node (ref "C7") (pin "2") (pinfunction "2_2") (pintype "input"))
      (node (ref "C8") (pin "1") (pinfunction "1_1") (pintype "input"))
      (node (ref "CN1") (pin "4") (pinfunction "4_4") (pintype "input"))
      (node (ref "Q1") (pin "3") (pinfunction "C_3") (pintype "input"))
      (node (ref "Q2") (pin "3") (pinfunction "C_3") (pintype "input"))
      (node (ref "Q3") (pin "3") (pinfunction "C_3") (pintype "input"))
      (node (ref "Q4") (pin "3") (pinfunction "C_3") (pintype "input"))
      (node (ref "R1") (pin "1") (pinfunction "1_1") (pintype "input"))
      (node (ref "R11") (pin "2") (pinfunction "2_2") (pintype "input"))
      (node (ref "R12") (pin "2") (pinfunction "2_2") (pintype "input"))
      (node (ref "R13") (pin "2") (pinfunction "2_2") (pintype "input"))
      (node (ref "R14") (pin "1") (pinfunction "1_1") (pintype "input"))
      (node (ref "R17") (pin "1") (pinfunction "1_1") (pintype "input"))
      (node (ref "R18") (pin "1") (pinfunction "1_1") (pintype "input"))
      (node (ref "R19") (pin "1") (pinfunction "1_1") (pintype "input"))
      (node (ref "R2") (pin "1") (pinfunction "1_1") (pintype "input"))
      (node (ref "R20") (pin "1") (pinfunction "1_1") (pintype "input"))
      (node (ref "R3") (pin "1") (pinfunction "1_1") (pintype "input"))
      (node (ref "R4") (pin "1") (pinfunction "1_1") (pintype "input"))
      (node (ref "R5") (pin "1") (pinfunction "1_1") (pintype "input"))
      (node (ref "R6") (pin "1") (pinfunction "1_1") (pintype "input"))
      (node (ref "R7") (pin "1") (pinfunction "1_1") (pintype "input"))
      (node (ref "R8") (pin "1") (pinfunction "1_1") (pintype "input"))
      (node (ref "R9") (pin "3") (pinfunction "3_3") (pintype "input"))
      (node (ref "SW1") (pin "1") (pinfunction "1_1") (pintype "input"))
      (node (ref "U1") (pin "1") (pinfunction "REF+_1") (pintype "input"))
      (node (ref "U1") (pin "8") (pinfunction "VCC_8") (pintype "input"))
      (node (ref "U2") (pin "2") (pinfunction "VOUT_2") (pintype "input"))
      (node (ref "U3") (pin "38") (pinfunction "VCC_38") (pintype "input"))
      (node (ref "U4") (pin "8") (pinfunction "VDD_8") (pintype "input"))
    )
    (net (code "72") (name "unconnected-(CN1-Pad5)") (class "Default")
      (node (ref "CN1") (pin "5") (pinfunction "5_5") (pintype "input+no_connect"))
    )
    (net (code "73") (name "unconnected-(CN1-Pad6)") (class "Default")
      (node (ref "CN1") (pin "6") (pinfunction "6_6") (pintype "input+no_connect"))
    )
    (net (code "74") (name "unconnected-(CN2-Pad3)") (class "Default")
      (node (ref "CN2") (pin "3") (pinfunction "3_3") (pintype "input+no_connect"))
    )
    (net (code "75") (name "unconnected-(CN2-Pad4)") (class "Default")
      (node (ref "CN2") (pin "4") (pinfunction "4_4") (pintype "input+no_connect"))
    )
    (net (code "76") (name "unconnected-(U3-EA#{slash}P4.6-Pad29)") (class "Default")
      (node (ref "U3") (pin "29") (pinfunction "EA#/P4.6_29") (pintype "input+no_connect"))
    )
    (net (code "77") (name "unconnected-(U4-DOUT-Pad4)") (class "Default")
      (node (ref "U4") (pin "4") (pinfunction "DOUT_4") (pintype "input+no_connect"))
    )
  )
)
